# bar_graph_blog_post.net
KiCad netlist of a schematic drawn in EAGLE
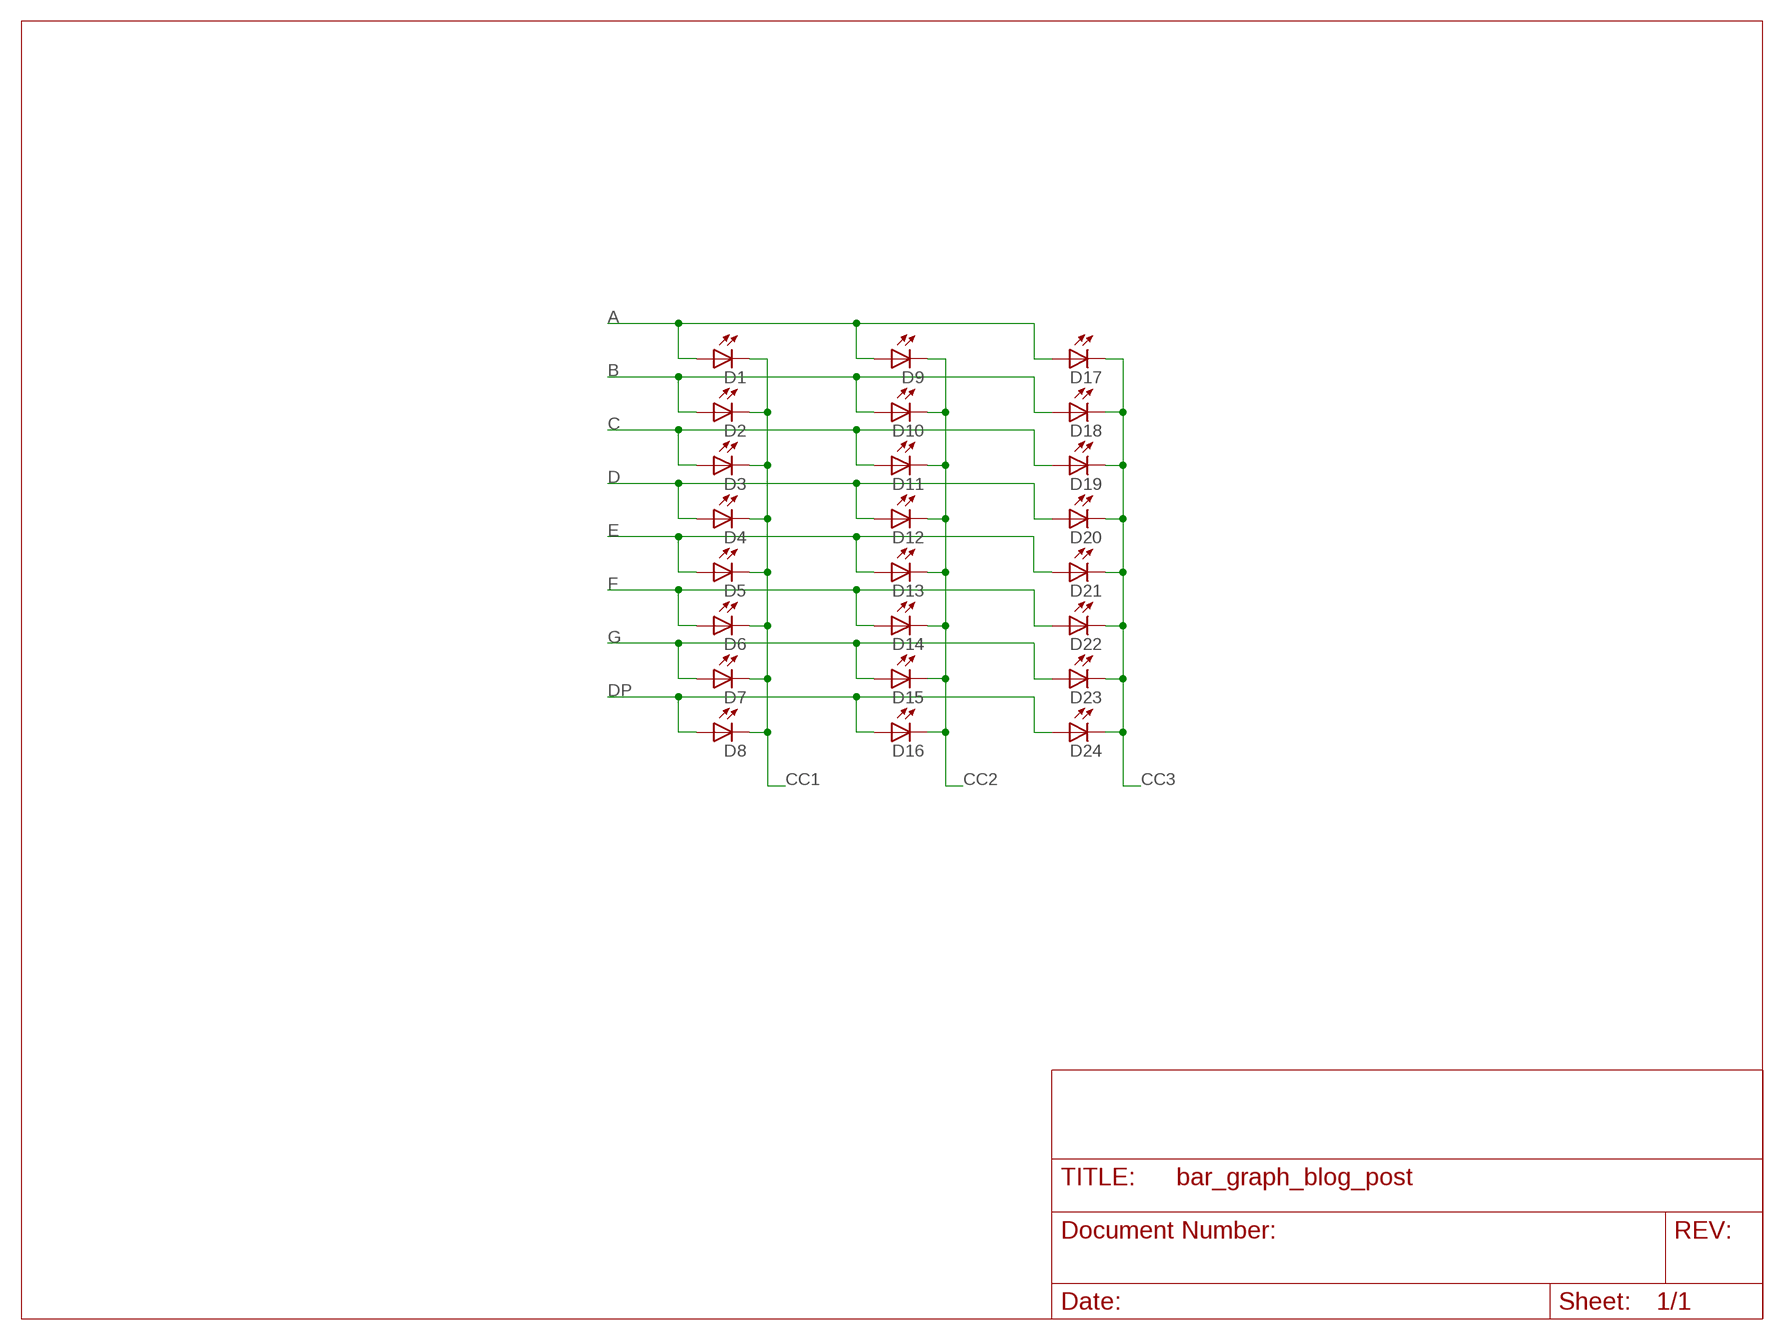
[diagram p0: schematic, sheet 1]

(export (version "E")
  (design (tool "Eeschema 10.0.6"))
  (components
    (comp (ref "D1")
      (value "LEDSQR2X5")
      (footprint "eagle-import:LED2X5")
      (libsource (lib "eagle-import") (part "LEDSQR2X5"))
    )
    (comp (ref "D2")
      (value "LEDSQR2X5")
      (footprint "eagle-import:LED2X5")
      (libsource (lib "eagle-import") (part "LEDSQR2X5"))
    )
    (comp (ref "D3")
      (value "LEDSQR2X5")
      (footprint "eagle-import:LED2X5")
      (libsource (lib "eagle-import") (part "LEDSQR2X5"))
    )
    (comp (ref "D4")
      (value "LEDSQR2X5")
      (footprint "eagle-import:LED2X5")
      (libsource (lib "eagle-import") (part "LEDSQR2X5"))
    )
    (comp (ref "D5")
      (value "LEDSQR2X5")
      (footprint "eagle-import:LED2X5")
      (libsource (lib "eagle-import") (part "LEDSQR2X5"))
    )
    (comp (ref "D6")
      (value "LEDSQR2X5")
      (footprint "eagle-import:LED2X5")
      (libsource (lib "eagle-import") (part "LEDSQR2X5"))
    )
    (comp (ref "D7")
      (value "LEDSQR2X5")
      (footprint "eagle-import:LED2X5")
      (libsource (lib "eagle-import") (part "LEDSQR2X5"))
    )
    (comp (ref "D8")
      (value "LEDSQR2X5")
      (footprint "eagle-import:LED2X5")
      (libsource (lib "eagle-import") (part "LEDSQR2X5"))
    )
    (comp (ref "D9")
      (value "LEDSQR2X5")
      (footprint "eagle-import:LED2X5")
      (libsource (lib "eagle-import") (part "LEDSQR2X5"))
    )
    (comp (ref "D10")
      (value "LEDSQR2X5")
      (footprint "eagle-import:LED2X5")
      (libsource (lib "eagle-import") (part "LEDSQR2X5"))
    )
    (comp (ref "D11")
      (value "LEDSQR2X5")
      (footprint "eagle-import:LED2X5")
      (libsource (lib "eagle-import") (part "LEDSQR2X5"))
    )
    (comp (ref "D12")
      (value "LEDSQR2X5")
      (footprint "eagle-import:LED2X5")
      (libsource (lib "eagle-import") (part "LEDSQR2X5"))
    )
    (comp (ref "D13")
      (value "LEDSQR2X5")
      (footprint "eagle-import:LED2X5")
      (libsource (lib "eagle-import") (part "LEDSQR2X5"))
    )
    (comp (ref "D14")
      (value "LEDSQR2X5")
      (footprint "eagle-import:LED2X5")
      (libsource (lib "eagle-import") (part "LEDSQR2X5"))
    )
    (comp (ref "D15")
      (value "LEDSQR2X5")
      (footprint "eagle-import:LED2X5")
      (libsource (lib "eagle-import") (part "LEDSQR2X5"))
    )
    (comp (ref "D16")
      (value "LEDSQR2X5")
      (footprint "eagle-import:LED2X5")
      (libsource (lib "eagle-import") (part "LEDSQR2X5"))
    )
    (comp (ref "D17")
      (value "LEDSQR2X5")
      (footprint "eagle-import:LED2X5")
      (libsource (lib "eagle-import") (part "LEDSQR2X5"))
    )
    (comp (ref "D18")
      (value "LEDSQR2X5")
      (footprint "eagle-import:LED2X5")
      (libsource (lib "eagle-import") (part "LEDSQR2X5"))
    )
    (comp (ref "D19")
      (value "LEDSQR2X5")
      (footprint "eagle-import:LED2X5")
      (libsource (lib "eagle-import") (part "LEDSQR2X5"))
    )
    (comp (ref "D20")
      (value "LEDSQR2X5")
      (footprint "eagle-import:LED2X5")
      (libsource (lib "eagle-import") (part "LEDSQR2X5"))
    )
    (comp (ref "D21")
      (value "LEDSQR2X5")
      (footprint "eagle-import:LED2X5")
      (libsource (lib "eagle-import") (part "LEDSQR2X5"))
    )
    (comp (ref "D22")
      (value "LEDSQR2X5")
      (footprint "eagle-import:LED2X5")
      (libsource (lib "eagle-import") (part "LEDSQR2X5"))
    )
    (comp (ref "D23")
      (value "LEDSQR2X5")
      (footprint "eagle-import:LED2X5")
      (libsource (lib "eagle-import") (part "LEDSQR2X5"))
    )
    (comp (ref "D24")
      (value "LEDSQR2X5")
      (footprint "eagle-import:LED2X5")
      (libsource (lib "eagle-import") (part "LEDSQR2X5"))
    )
  )
  (nets
    (net (code "1") (name "/A") (class "Default")
      (node (ref "D1") (pin "A") (pinfunction "A_A") (pintype "passive"))
      (node (ref "D17") (pin "A") (pinfunction "A_A") (pintype "passive"))
      (node (ref "D9") (pin "A") (pinfunction "A_A") (pintype "passive"))
    )
    (net (code "2") (name "/B") (class "Default")
      (node (ref "D10") (pin "A") (pinfunction "A_A") (pintype "passive"))
      (node (ref "D18") (pin "A") (pinfunction "A_A") (pintype "passive"))
      (node (ref "D2") (pin "A") (pinfunction "A_A") (pintype "passive"))
    )
    (net (code "3") (name "/C") (class "Default")
      (node (ref "D11") (pin "A") (pinfunction "A_A") (pintype "passive"))
      (node (ref "D19") (pin "A") (pinfunction "A_A") (pintype "passive"))
      (node (ref "D3") (pin "A") (pinfunction "A_A") (pintype "passive"))
    )
    (net (code "4") (name "/CC1") (class "Default")
      (node (ref "D1") (pin "K") (pinfunction "C_K") (pintype "passive"))
      (node (ref "D2") (pin "K") (pinfunction "C_K") (pintype "passive"))
      (node (ref "D3") (pin "K") (pinfunction "C_K") (pintype "passive"))
      (node (ref "D4") (pin "K") (pinfunction "C_K") (pintype "passive"))
      (node (ref "D5") (pin "K") (pinfunction "C_K") (pintype "passive"))
      (node (ref "D6") (pin "K") (pinfunction "C_K") (pintype "passive"))
      (node (ref "D7") (pin "K") (pinfunction "C_K") (pintype "passive"))
      (node (ref "D8") (pin "K") (pinfunction "C_K") (pintype "passive"))
    )
    (net (code "5") (name "/CC2") (class "Default")
      (node (ref "D10") (pin "K") (pinfunction "C_K") (pintype "passive"))
      (node (ref "D11") (pin "K") (pinfunction "C_K") (pintype "passive"))
      (node (ref "D12") (pin "K") (pinfunction "C_K") (pintype "passive"))
      (node (ref "D13") (pin "K") (pinfunction "C_K") (pintype "passive"))
      (node (ref "D14") (pin "K") (pinfunction "C_K") (pintype "passive"))
      (node (ref "D15") (pin "K") (pinfunction "C_K") (pintype "passive"))
      (node (ref "D16") (pin "K") (pinfunction "C_K") (pintype "passive"))
      (node (ref "D9") (pin "K") (pinfunction "C_K") (pintype "passive"))
    )
    (net (code "6") (name "/CC3") (class "Default")
      (node (ref "D17") (pin "K") (pinfunction "C_K") (pintype "passive"))
      (node (ref "D18") (pin "K") (pinfunction "C_K") (pintype "passive"))
      (node (ref "D19") (pin "K") (pinfunction "C_K") (pintype "passive"))
      (node (ref "D20") (pin "K") (pinfunction "C_K") (pintype "passive"))
      (node (ref "D21") (pin "K") (pinfunction "C_K") (pintype "passive"))
      (node (ref "D22") (pin "K") (pinfunction "C_K") (pintype "passive"))
      (node (ref "D23") (pin "K") (pinfunction "C_K") (pintype "passive"))
      (node (ref "D24") (pin "K") (pinfunction "C_K") (pintype "passive"))
    )
    (net (code "7") (name "/D") (class "Default")
      (node (ref "D12") (pin "A") (pinfunction "A_A") (pintype "passive"))
      (node (ref "D20") (pin "A") (pinfunction "A_A") (pintype "passive"))
      (node (ref "D4") (pin "A") (pinfunction "A_A") (pintype "passive"))
    )
    (net (code "8") (name "/DP") (class "Default")
      (node (ref "D16") (pin "A") (pinfunction "A_A") (pintype "passive"))
      (node (ref "D24") (pin "A") (pinfunction "A_A") (pintype "passive"))
      (node (ref "D8") (pin "A") (pinfunction "A_A") (pintype "passive"))
    )
    (net (code "9") (name "/E") (class "Default")
      (node (ref "D13") (pin "A") (pinfunction "A_A") (pintype "passive"))
      (node (ref "D21") (pin "A") (pinfunction "A_A") (pintype "passive"))
      (node (ref "D5") (pin "A") (pinfunction "A_A") (pintype "passive"))
    )
    (net (code "10") (name "/F") (class "Default")
      (node (ref "D14") (pin "A") (pinfunction "A_A") (pintype "passive"))
      (node (ref "D22") (pin "A") (pinfunction "A_A") (pintype "passive"))
      (node (ref "D6") (pin "A") (pinfunction "A_A") (pintype "passive"))
    )
    (net (code "11") (name "/G") (class "Default")
      (node (ref "D15") (pin "A") (pinfunction "A_A") (pintype "passive"))
      (node (ref "D23") (pin "A") (pinfunction "A_A") (pintype "passive"))
      (node (ref "D7") (pin "A") (pinfunction "A_A") (pintype "passive"))
    )
  )
)
